# 6coils-1-discrete.net
KiCad netlist of a schematic drawn in EasyEDA
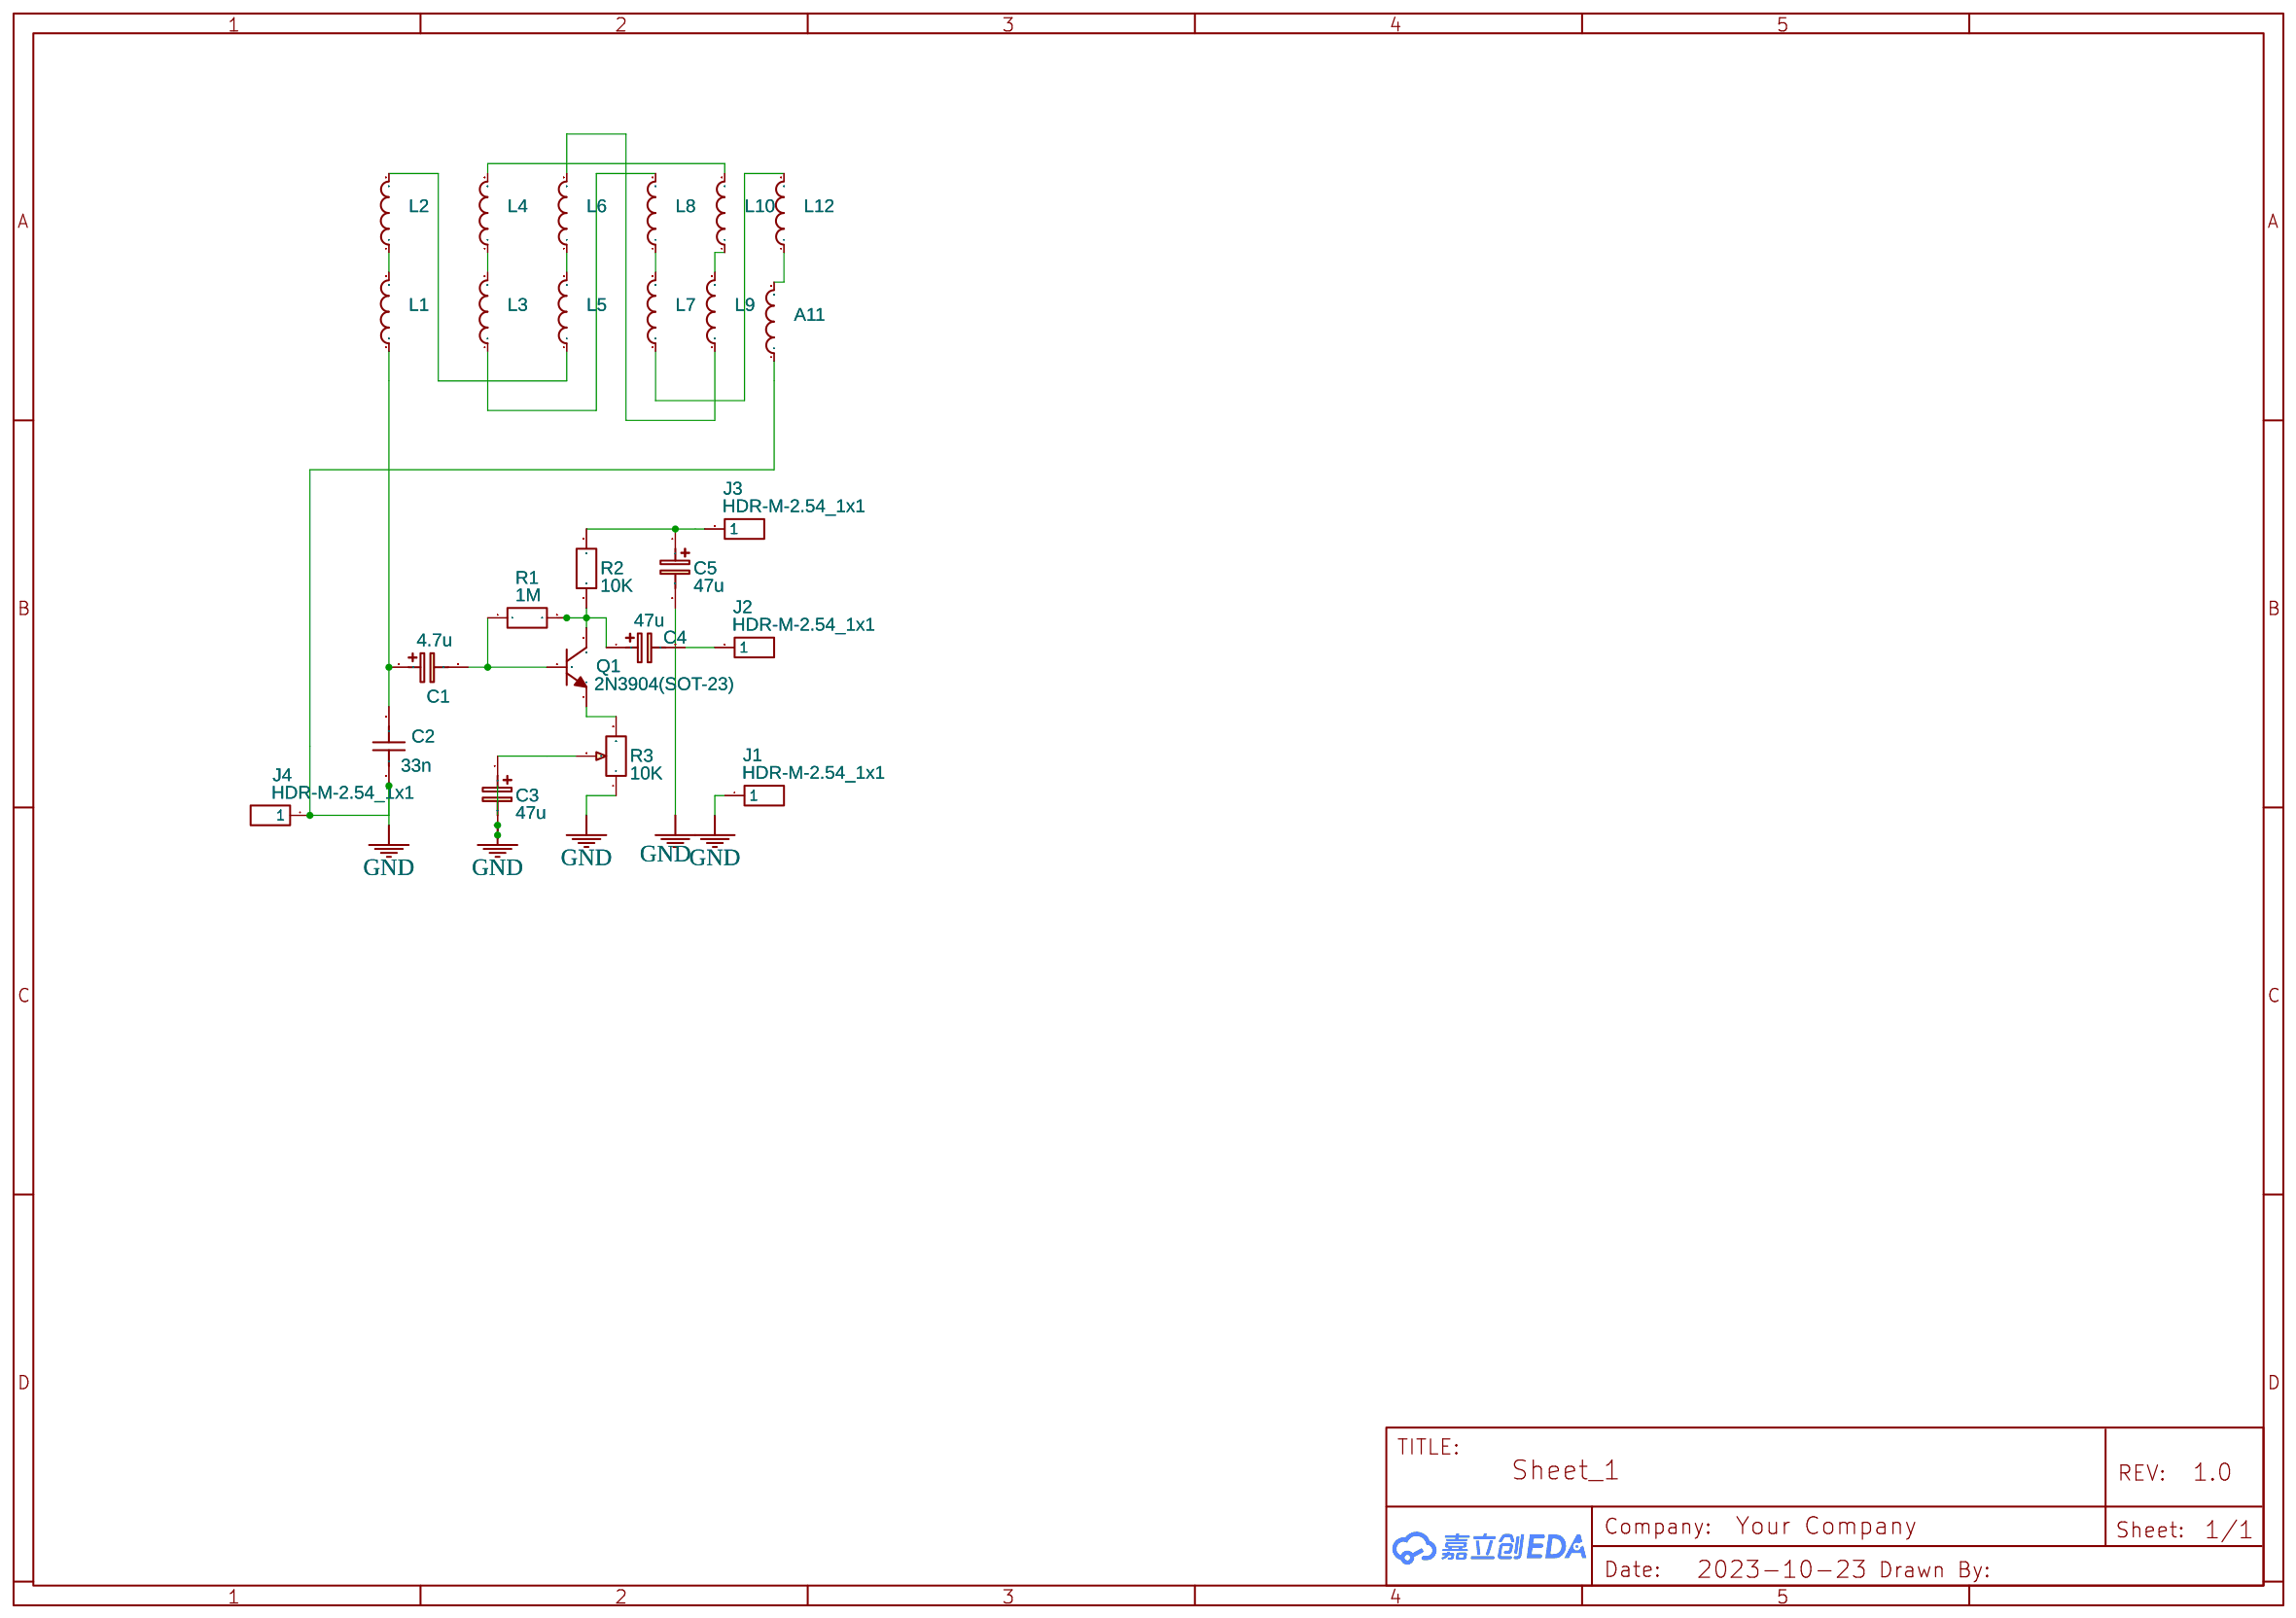
[diagram p0: schematic sheet]

(export (version "E")
  (design (tool "Eeschema 10.0.6"))
  (components
    (comp (ref "A11")
      (value "INDUCTOR_SMD:L_COILCRAFT_XXL4040")
      (fields (field (name "Manufacturer Part") "Inductor_SMD:L_Coilcraft_XxL4040"))
      (libsource (lib "") (part "INDUCTOR_SMD{colon}L_COILCRAFT_XXL4040_1"))
    )
    (comp (ref "C1") (value "4.7u") (libsource (lib "") (part "C_Tan_SMD_A_EU")))
    (comp (ref "C2") (value "33n") (libsource (lib "") (part "C_0603_US")))
    (comp (ref "C3") (value "47u") (libsource (lib "") (part "C_Tan_SMD_A_EU_2")))
    (comp (ref "C4") (value "47u") (libsource (lib "") (part "C_Tan_SMD_A_EU_1")))
    (comp (ref "C5") (value "47u") (libsource (lib "") (part "C_Tan_SMD_A_EU_3")))
    (comp (ref "J1")
      (value "HDR-M-2.54_1x1")
      (fields (field (name "BOM_Supplier Part") "C81276"))
      (libsource (lib "") (part "HDR-M-2.54_1x1"))
    )
    (comp (ref "J2")
      (value "HDR-M-2.54_1x1")
      (fields (field (name "BOM_Supplier Part") "C81276"))
      (libsource (lib "") (part "HDR-M-2.54_1x1"))
    )
    (comp (ref "J3")
      (value "HDR-M-2.54_1x1")
      (fields (field (name "BOM_Supplier Part") "C81276"))
      (libsource (lib "") (part "HDR-M-2.54_1x1"))
    )
    (comp (ref "J4")
      (value "HDR-M-2.54_1x1")
      (fields (field (name "BOM_Supplier Part") "C81276"))
      (libsource (lib "") (part "HDR-M-2.54_1x1_1"))
    )
    (comp (ref "L1")
      (value "INDUCTOR_SMD:L_COILCRAFT_XXL4040")
      (fields (field (name "Manufacturer Part") "Inductor_SMD:L_Coilcraft_XxL4040"))
      (libsource (lib "") (part "INDUCTOR_SMD{colon}L_COILCRAFT_XXL4040_2"))
    )
    (comp (ref "L2")
      (value "INDUCTOR_SMD:L_COILCRAFT_XXL4040")
      (fields (field (name "Manufacturer Part") "Inductor_SMD:L_Coilcraft_XxL4040"))
      (libsource (lib "") (part "INDUCTOR_SMD{colon}L_COILCRAFT_XXL4040_2"))
    )
    (comp (ref "L3")
      (value "INDUCTOR_SMD:L_COILCRAFT_XXL4040")
      (fields (field (name "Manufacturer Part") "Inductor_SMD:L_Coilcraft_XxL4040"))
      (libsource (lib "") (part "INDUCTOR_SMD{colon}L_COILCRAFT_XXL4040_2"))
    )
    (comp (ref "L4")
      (value "INDUCTOR_SMD:L_COILCRAFT_XXL4040")
      (fields (field (name "Manufacturer Part") "Inductor_SMD:L_Coilcraft_XxL4040"))
      (libsource (lib "") (part "INDUCTOR_SMD{colon}L_COILCRAFT_XXL4040_2"))
    )
    (comp (ref "L5")
      (value "INDUCTOR_SMD:L_COILCRAFT_XXL4040")
      (fields (field (name "Manufacturer Part") "Inductor_SMD:L_Coilcraft_XxL4040"))
      (libsource (lib "") (part "INDUCTOR_SMD{colon}L_COILCRAFT_XXL4040"))
    )
    (comp (ref "L6")
      (value "INDUCTOR_SMD:L_COILCRAFT_XXL4040")
      (fields (field (name "Manufacturer Part") "Inductor_SMD:L_Coilcraft_XxL4040"))
      (libsource (lib "") (part "INDUCTOR_SMD{colon}L_COILCRAFT_XXL4040"))
    )
    (comp (ref "L7")
      (value "INDUCTOR_SMD:L_COILCRAFT_XXL4040")
      (fields (field (name "Manufacturer Part") "Inductor_SMD:L_Coilcraft_XxL4040"))
      (libsource (lib "") (part "INDUCTOR_SMD{colon}L_COILCRAFT_XXL4040"))
    )
    (comp (ref "L8")
      (value "INDUCTOR_SMD:L_COILCRAFT_XXL4040")
      (fields (field (name "Manufacturer Part") "Inductor_SMD:L_Coilcraft_XxL4040"))
      (libsource (lib "") (part "INDUCTOR_SMD{colon}L_COILCRAFT_XXL4040"))
    )
    (comp (ref "L9")
      (value "INDUCTOR_SMD:L_COILCRAFT_XXL4040")
      (fields (field (name "Manufacturer Part") "Inductor_SMD:L_Coilcraft_XxL4040"))
      (libsource (lib "") (part "INDUCTOR_SMD{colon}L_COILCRAFT_XXL4040"))
    )
    (comp (ref "L10")
      (value "INDUCTOR_SMD:L_COILCRAFT_XXL4040")
      (fields (field (name "Manufacturer Part") "Inductor_SMD:L_Coilcraft_XxL4040"))
      (libsource (lib "") (part "INDUCTOR_SMD{colon}L_COILCRAFT_XXL4040"))
    )
    (comp (ref "L12")
      (value "INDUCTOR_SMD:L_COILCRAFT_XXL4040")
      (fields (field (name "Manufacturer Part") "Inductor_SMD:L_Coilcraft_XxL4040"))
      (libsource (lib "") (part "INDUCTOR_SMD{colon}L_COILCRAFT_XXL4040"))
    )
    (comp (ref "Q1")
      (value "2N3904(SOT-23)")
      (fields
        (field (name "BOM_Manufacturer Part") "2n3904S-RTK/PS")
        (field (name "BOM_Supplier Part") "C18536")
      )
      (libsource (lib "") (part "2N3904(SOT-23)"))
    )
    (comp (ref "R1") (value "1M") (libsource (lib "") (part "R_0603_EU")))
    (comp (ref "R2") (value "10K") (libsource (lib "") (part "R_0603_EU_1")))
    (comp (ref "R3")
      (value "10K")
      (fields (field (name "Manufacturer Part") "RM063-103 10K") (field (name "Manufacturer") "JML"))
      (libsource (lib "") (part "RM063-103 10K"))
    )
  )
  (nets
    (net (code "1") (name "GND") (class "Default")
      (node (ref "A11") (pin "1") (pinfunction "1_1") (pintype "unspecified"))
      (node (ref "C2") (pin "1") (pinfunction "1_1") (pintype "unspecified"))
      (node (ref "C3") (pin "2") (pinfunction "2_2") (pintype "unspecified"))
      (node (ref "C5") (pin "2") (pinfunction "2_2") (pintype "unspecified"))
      (node (ref "J1") (pin "1") (pinfunction "1_1") (pintype "input"))
      (node (ref "J4") (pin "1") (pinfunction "1_1") (pintype "input"))
      (node (ref "R3") (pin "1") (pinfunction "1_1") (pintype "input"))
    )
    (net (code "2") (name "Net-(A11-Pad2)") (class "Default")
      (node (ref "A11") (pin "2") (pinfunction "2_2") (pintype "unspecified"))
      (node (ref "L12") (pin "1") (pinfunction "1_1") (pintype "unspecified"))
    )
    (net (code "3") (name "Net-(C1-Pad1)") (class "Default")
      (node (ref "C1") (pin "1") (pinfunction "1_1") (pintype "unspecified"))
      (node (ref "C2") (pin "2") (pinfunction "2_2") (pintype "unspecified"))
      (node (ref "L1") (pin "1") (pinfunction "1_1") (pintype "unspecified"))
    )
    (net (code "4") (name "Net-(C3-Pad1)") (class "Default")
      (node (ref "C3") (pin "1") (pinfunction "1_1") (pintype "unspecified"))
      (node (ref "R3") (pin "2") (pinfunction "2_2") (pintype "input"))
    )
    (net (code "5") (name "Net-(C4-Pad2)") (class "Default")
      (node (ref "C4") (pin "2") (pinfunction "2_2") (pintype "unspecified"))
      (node (ref "J2") (pin "1") (pinfunction "1_1") (pintype "input"))
    )
    (net (code "6") (name "Net-(C5-Pad1)") (class "Default")
      (node (ref "C5") (pin "1") (pinfunction "1_1") (pintype "unspecified"))
      (node (ref "J3") (pin "1") (pinfunction "1_1") (pintype "input"))
      (node (ref "R2") (pin "2") (pinfunction "2_2") (pintype "unspecified"))
    )
    (net (code "7") (name "Net-(L1-Pad2)") (class "Default")
      (node (ref "L1") (pin "2") (pinfunction "2_2") (pintype "unspecified"))
      (node (ref "L2") (pin "1") (pinfunction "1_1") (pintype "unspecified"))
    )
    (net (code "8") (name "Net-(L2-Pad2)") (class "Default")
      (node (ref "L2") (pin "2") (pinfunction "2_2") (pintype "unspecified"))
      (node (ref "L5") (pin "1") (pinfunction "1_1") (pintype "unspecified"))
    )
    (net (code "9") (name "Net-(L3-Pad1)") (class "Default")
      (node (ref "L3") (pin "1") (pinfunction "1_1") (pintype "unspecified"))
      (node (ref "L8") (pin "2") (pinfunction "2_2") (pintype "unspecified"))
    )
    (net (code "10") (name "Net-(L3-Pad2)") (class "Default")
      (node (ref "L3") (pin "2") (pinfunction "2_2") (pintype "unspecified"))
      (node (ref "L4") (pin "1") (pinfunction "1_1") (pintype "unspecified"))
    )
    (net (code "11") (name "Net-(L5-Pad2)") (class "Default")
      (node (ref "L5") (pin "2") (pinfunction "2_2") (pintype "unspecified"))
      (node (ref "L6") (pin "1") (pinfunction "1_1") (pintype "unspecified"))
    )
    (net (code "12") (name "Net-(L6-Pad2)") (class "Default")
      (node (ref "L6") (pin "2") (pinfunction "2_2") (pintype "unspecified"))
      (node (ref "L9") (pin "1") (pinfunction "1_1") (pintype "unspecified"))
    )
    (net (code "13") (name "Net-(L7-Pad2)") (class "Default")
      (node (ref "L7") (pin "2") (pinfunction "2_2") (pintype "unspecified"))
      (node (ref "L8") (pin "1") (pinfunction "1_1") (pintype "unspecified"))
    )
    (net (code "14") (name "Net-(L10-Pad1)") (class "Default")
      (node (ref "L10") (pin "1") (pinfunction "1_1") (pintype "unspecified"))
      (node (ref "L9") (pin "2") (pinfunction "2_2") (pintype "unspecified"))
    )
    (net (code "15") (name "Net-(L10-Pad2)") (class "Default")
      (node (ref "L10") (pin "2") (pinfunction "2_2") (pintype "unspecified"))
      (node (ref "L4") (pin "2") (pinfunction "2_2") (pintype "unspecified"))
    )
    (net (code "16") (name "Net-(L12-Pad2)") (class "Default")
      (node (ref "L12") (pin "2") (pinfunction "2_2") (pintype "unspecified"))
      (node (ref "L7") (pin "1") (pinfunction "1_1") (pintype "unspecified"))
    )
    (net (code "17") (name "Net-(Q1-B)") (class "Default")
      (node (ref "C1") (pin "2") (pinfunction "2_2") (pintype "unspecified"))
      (node (ref "Q1") (pin "2") (pinfunction "B_2") (pintype "input"))
      (node (ref "R1") (pin "1") (pinfunction "1_1") (pintype "unspecified"))
    )
    (net (code "18") (name "Net-(Q1-C)") (class "Default")
      (node (ref "C4") (pin "1") (pinfunction "1_1") (pintype "unspecified"))
      (node (ref "Q1") (pin "3") (pinfunction "C_3") (pintype "input"))
      (node (ref "R1") (pin "2") (pinfunction "2_2") (pintype "unspecified"))
      (node (ref "R2") (pin "1") (pinfunction "1_1") (pintype "unspecified"))
    )
    (net (code "19") (name "Net-(Q1-E)") (class "Default")
      (node (ref "Q1") (pin "1") (pinfunction "E_1") (pintype "input"))
      (node (ref "R3") (pin "3") (pinfunction "3_3") (pintype "input"))
    )
  )
)
